# 846-XXXXX_SCH_NEO-M9N_MODULE_2_RECEIVER.net
KiCad netlist of a schematic drawn in Altium Designer
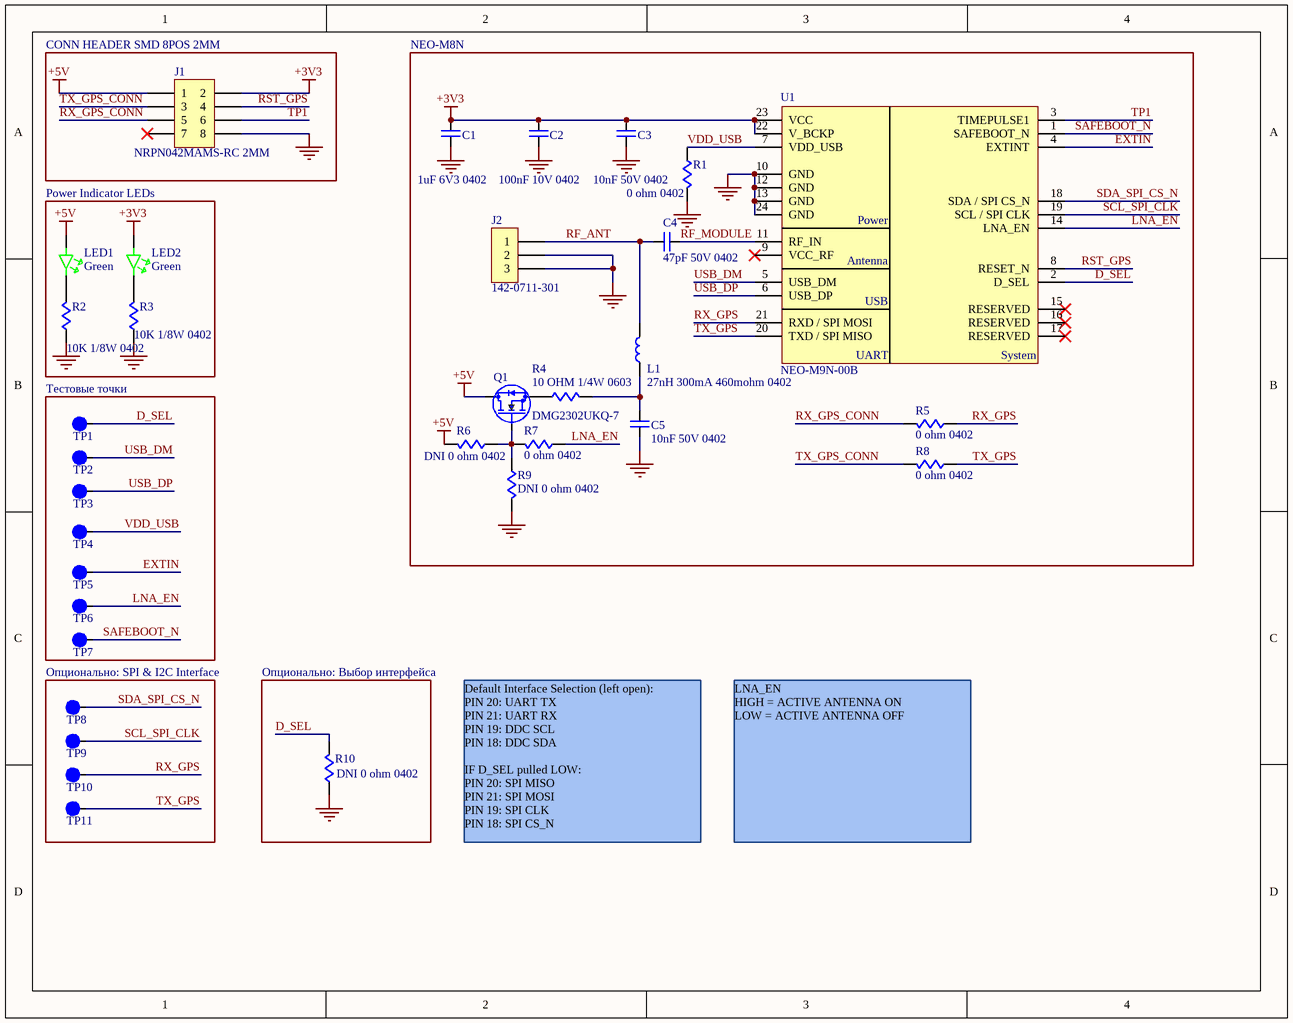
[diagram p0: 846-XXXXX_SCH_NEO-M9N_MODULE_2_RECEIVER.SchDoc]

(export (version "E")
  (design (tool "Eeschema 10.0.6"))
  (components
    (comp (ref "C1")
      (value "1uF 6V3 0402")
      (footprint "c0402")
      (description "0402 1 uF 6.3 V ±10% Tolerance X7R Multilayer Ceramic Capacitor")
      (fields
        (field (name "MANUFACTURER") "Murata")
        (field (name "MANUFACTURER PART NUMBER") "GRM155R70J105KA12J")
      )
      (libsource (lib "MyLibrary") (part "CAP CER 1UF 6.3V X7R 0402"))
    )
    (comp (ref "C2")
      (value "100nF 10V 0402")
      (footprint "c0402")
      (description "CL05 Series 0.1 uF 10 V ±10 % Tolerance X7R SMT Multilayer Ceramic Capacitor")
      (fields
        (field (name "MANUFACTURER") "Samsung")
        (field (name "MANUFACTURER PART NUMBER") "CL05B104KP5NNNC")
      )
      (libsource (lib "MyLibrary") (part "CAP CER 0.1UF 10V X7R 0402"))
    )
    (comp (ref "C3")
      (value "10nF 50V 0402")
      (footprint "c0402")
      (description "CAP CER 10000PF 50V X7R 0402")
      (fields
        (field (name "MANUFACTURER") "Murata")
        (field (name "MANUFACTURER PART NUMBER") "GCM155R71H103KA55D")
      )
      (libsource (lib "MyLibrary") (part "CAP CER 10000PF 50V X7R 0402"))
    )
    (comp (ref "C4")
      (value "47pF 50V 0402")
      (footprint "c0402")
      (description "0402 47 pF 50 V ±5 % Tolerance NP0 SMT Multilayer Ceramic Capacitor")
      (fields
        (field (name "MANUFACTURER") "Yageo")
        (field (name "MANUFACTURER PART NUMBER") "CC0402JRNPO9BN470")
      )
      (libsource (lib "MyLibrary") (part "CAP CER 47PF 50V C0G/NPO 0402"))
    )
    (comp (ref "C5")
      (value "10nF 50V 0402")
      (footprint "c0402")
      (description "CAP CER 10000PF 50V X7R 0402")
      (fields
        (field (name "MANUFACTURER") "Murata")
        (field (name "MANUFACTURER PART NUMBER") "GCM155R71H103KA55D")
      )
      (libsource (lib "MyLibrary") (part "CAP CER 10000PF 50V X7R 0402"))
    )
    (comp (ref "J1")
      (value "NRPN042MAMS-RC 2MM")
      (footprint "CONN_NRPN042MAMS-RC")
      (description "Dual Row 8 Position 2 mm Pitch Surface Mount Header")
      (fields
        (field (name "MANUFACTURER") "Sullins")
        (field (name "MANUFACTURER PART NUMBER") "NRPN042MAMS-RC")
      )
      (libsource (lib "MyLibrary") (part "CONN_NRPN042MAMS-RC"))
    )
    (comp (ref "J2")
      (value "142-0711-301")
      (footprint "CONN_131-3711-301")
      (description "Rf Coaxial Board Mount Connector")
      (fields
        (field (name "MANUFACTURER") "Bel Cinch")
        (field (name "MANUFACTURER PART NUMBER") "131-3711-301")
      )
      (libsource (lib "MyLibrary") (part "CONN_131-3711-301"))
    )
    (comp (ref "L1")
      (value "27nH 300mA 460mohm 0402")
      (footprint "L0402")
      (description "Inductor RF Chip Multi-Layer 27nH 5% 100MHz 8Q-Factor Air 300mA 460mOhm DCR 0402 Paper T/R")
      (fields
        (field (name "MANUFACTURER") "Murata")
        (field (name "MANUFACTURER PART NUMBER") "LQG15HS27NJ02D")
      )
      (libsource (lib "MyLibrary") (part "FIXED IND 27NH 350MA 460MOHM SMD"))
    )
    (comp (ref "LED1")
      (value "Green")
      (footprint "led0603")
      (description "LED High-Power Uni-Color Green 574nm 2-Pin Chip LED T/R")
      (fields
        (field (name "MANUFACTURER") "Vishay Lite-On")
        (field (name "MANUFACTURER PART NUMBER") "LTST-C190KGKT")
      )
      (libsource (lib "MyLibrary") (part "LED GREEN CLEAR CHIP SMD"))
    )
    (comp (ref "LED2")
      (value "Green")
      (footprint "led0603")
      (description "LED High-Power Uni-Color Green 574nm 2-Pin Chip LED T/R")
      (fields
        (field (name "MANUFACTURER") "Vishay Lite-On")
        (field (name "MANUFACTURER PART NUMBER") "LTST-C190KGKT")
      )
      (libsource (lib "MyLibrary") (part "LED GREEN CLEAR CHIP SMD"))
    )
    (comp (ref "Q1")
      (value "DMG2302UKQ-7")
      (footprint "SOT23")
      (description "N-Channel 20 V 2.8A (Ta) 660mW (Ta) Surface Mount SOT-23-3")
      (fields
        (field (name "MANUFACTURER") "Diodes")
        (field (name "COPYRIGHT") "Copyright (C) 2022 Ultra Librarian. All rights reserved.")
      )
      (libsource (lib "MyLibrary") (part "DMG2302UKQ-7"))
    )
    (comp (ref "R1")
      (value "0 ohm 0402")
      (footprint "r0402")
      (description "RES SMD 0 OHM JUMPER 1/16W 0402")
      (fields
        (field (name "MANUFACTURER") "Yageo")
        (field (name "MANUFACTURER PART NUMBER") "RC0402JR-070RL")
      )
      (libsource (lib "MyLibrary") (part "RES 0 OHM JUMPER 1/16W 0402"))
    )
    (comp (ref "R2")
      (value "10K 1/8W 0402")
      (footprint "r0402")
      (description "Res Thick Film 0402 10K Ohm 1% 0.125W(1/8W) ±100ppm/°C Pad SMD T/R")
      (fields
        (field (name "MANUFACTURER") "TE Connectivity")
        (field (name "MANUFACTURER PART NUMBER") "CRGP0402F10K")
      )
      (libsource (lib "MyLibrary") (part "RES 10K OHM 1% 1/8W 0402"))
    )
    (comp (ref "R3")
      (value "10K 1/8W 0402")
      (footprint "r0402")
      (description "Res Thick Film 0402 10K Ohm 1% 0.125W(1/8W) ±100ppm/°C Pad SMD T/R")
      (fields
        (field (name "MANUFACTURER") "TE Connectivity")
        (field (name "MANUFACTURER PART NUMBER") "CRGP0402F10K")
      )
      (libsource (lib "MyLibrary") (part "RES 10K OHM 1% 1/8W 0402"))
    )
    (comp (ref "R4")
      (value "10 OHM 1/4W 0603")
      (footprint "r0603")
      (description "Res Surge Chip Thick Film 0603 10 Ohm 1% 1/4W ±200ppm/°C Molded Paper T/R")
      (fields
        (field (name "MANUFACTURER") "Yageo")
        (field (name "MANUFACTURER PART NUMBER") "SR0603FR-7T10RL")
      )
      (libsource (lib "MyLibrary") (part "RES SMD 10 OHM 1% 1/4W 0603"))
    )
    (comp (ref "R5")
      (value "0 ohm 0402")
      (footprint "r0402")
      (description "RES SMD 0 OHM JUMPER 1/16W 0402")
      (fields
        (field (name "MANUFACTURER") "Yageo")
        (field (name "MANUFACTURER PART NUMBER") "RC0402JR-070RL")
      )
      (libsource (lib "MyLibrary") (part "RES 0 OHM JUMPER 1/16W 0402"))
    )
    (comp (ref "R6")
      (value "DNI 0 ohm 0402")
      (footprint "r0402")
      (description "RES SMD 0 OHM JUMPER 1/16W 0402")
      (fields
        (field (name "MANUFACTURER") "Yageo")
        (field (name "MANUFACTURER PART NUMBER") "RC0402JR-070RL")
      )
      (libsource (lib "MyLibrary") (part "RES 0 OHM JUMPER 1/16W 0402"))
    )
    (comp (ref "R7")
      (value "0 ohm 0402")
      (footprint "r0402")
      (description "RES SMD 0 OHM JUMPER 1/16W 0402")
      (fields
        (field (name "MANUFACTURER") "Yageo")
        (field (name "MANUFACTURER PART NUMBER") "RC0402JR-070RL")
      )
      (libsource (lib "MyLibrary") (part "RES 0 OHM JUMPER 1/16W 0402"))
    )
    (comp (ref "R8")
      (value "0 ohm 0402")
      (footprint "r0402")
      (description "RES SMD 0 OHM JUMPER 1/16W 0402")
      (fields
        (field (name "MANUFACTURER") "Yageo")
        (field (name "MANUFACTURER PART NUMBER") "RC0402JR-070RL")
      )
      (libsource (lib "MyLibrary") (part "RES 0 OHM JUMPER 1/16W 0402"))
    )
    (comp (ref "R9")
      (value "DNI 0 ohm 0402")
      (footprint "r0402")
      (description "RES SMD 0 OHM JUMPER 1/16W 0402")
      (fields
        (field (name "MANUFACTURER") "Yageo")
        (field (name "MANUFACTURER PART NUMBER") "RC0402JR-070RL")
      )
      (libsource (lib "MyLibrary") (part "RES 0 OHM JUMPER 1/16W 0402"))
    )
    (comp (ref "R10")
      (value "DNI 0 ohm 0402")
      (footprint "r0402")
      (description "RES SMD 0 OHM JUMPER 1/16W 0402")
      (fields
        (field (name "MANUFACTURER") "Yageo")
        (field (name "MANUFACTURER PART NUMBER") "RC0402JR-070RL")
      )
      (libsource (lib "MyLibrary") (part "RES 0 OHM JUMPER 1/16W 0402"))
    )
    (comp (ref "TP1")
      (value "1MM")
      (footprint "TP1MM")
      (description "Test Point 1MM diameter")
      (libsource (lib "MyLibrary") (part "TP_1MM"))
    )
    (comp (ref "TP2")
      (value "1MM")
      (footprint "TP1MM")
      (description "Test Point 1MM diameter")
      (libsource (lib "MyLibrary") (part "TP_1MM"))
    )
    (comp (ref "TP3")
      (value "1MM")
      (footprint "TP1MM")
      (description "Test Point 1MM diameter")
      (libsource (lib "MyLibrary") (part "TP_1MM"))
    )
    (comp (ref "TP4")
      (value "1MM")
      (footprint "TP1MM")
      (description "Test Point 1MM diameter")
      (libsource (lib "MyLibrary") (part "TP_1MM"))
    )
    (comp (ref "TP5")
      (value "1MM")
      (footprint "TP1MM")
      (description "Test Point 1MM diameter")
      (libsource (lib "MyLibrary") (part "TP_1MM"))
    )
    (comp (ref "TP6")
      (value "1MM")
      (footprint "TP1MM")
      (description "Test Point 1MM diameter")
      (libsource (lib "MyLibrary") (part "TP_1MM"))
    )
    (comp (ref "TP7")
      (value "1MM")
      (footprint "TP1MM")
      (description "Test Point 1MM diameter")
      (libsource (lib "MyLibrary") (part "TP_1MM"))
    )
    (comp (ref "TP8")
      (value "1MM")
      (footprint "TP1MM")
      (description "Test Point 1MM diameter")
      (libsource (lib "MyLibrary") (part "TP_1MM"))
    )
    (comp (ref "TP9")
      (value "1MM")
      (footprint "TP1MM")
      (description "Test Point 1MM diameter")
      (libsource (lib "MyLibrary") (part "TP_1MM"))
    )
    (comp (ref "TP10")
      (value "1MM")
      (footprint "TP1MM")
      (description "Test Point 1MM diameter")
      (libsource (lib "MyLibrary") (part "TP_1MM"))
    )
    (comp (ref "TP11")
      (value "1MM")
      (footprint "TP1MM")
      (description "Test Point 1MM diameter")
      (libsource (lib "MyLibrary") (part "TP_1MM"))
    )
    (comp (ref "U1")
      (value "NEO-M9N-00B")
      (footprint "IC_NEO-M9N")
      (description "GNSS module, Flash, TCXO, SAW, LNA, LCC, 12x16 mm Professional Grade")
      (fields (field (name "MANUFACTURER") "u-blox"))
      (libsource (lib "MyLibrary") (part "IC NEO-M9N-00B"))
    )
  )
  (nets
    (net (code "1") (name "+3V3") (class "Default")
      (node (ref "C1") (pin "2") (pinfunction "2_2") (pintype "passive"))
      (node (ref "C2") (pin "2") (pinfunction "2_2") (pintype "passive"))
      (node (ref "C3") (pin "2") (pinfunction "2_2") (pintype "passive"))
      (node (ref "J1") (pin "2") (pinfunction "2_2") (pintype "passive"))
      (node (ref "LED2") (pin "1") (pinfunction "1_1") (pintype "passive"))
      (node (ref "U1") (pin "22") (pinfunction "V_BCKP_22") (pintype "passive"))
      (node (ref "U1") (pin "23") (pinfunction "VCC_23") (pintype "passive"))
    )
    (net (code "2") (name "+5V") (class "Default")
      (node (ref "J1") (pin "1") (pinfunction "1_1") (pintype "passive"))
      (node (ref "LED1") (pin "1") (pinfunction "1_1") (pintype "passive"))
      (node (ref "Q1") (pin "2") (pinfunction "D_2") (pintype "passive"))
      (node (ref "R6") (pin "2") (pinfunction "2_2") (pintype "passive"))
    )
    (net (code "3") (name "/D_SEL") (class "Default")
      (node (ref "R10") (pin "2") (pinfunction "2_2") (pintype "passive"))
      (node (ref "TP1") (pin "1") (pinfunction "1_1") (pintype "passive"))
      (node (ref "U1") (pin "2") (pinfunction "D_SEL_2") (pintype "passive"))
    )
    (net (code "4") (name "/EXTIN") (class "Default")
      (node (ref "TP5") (pin "1") (pinfunction "1_1") (pintype "passive"))
      (node (ref "U1") (pin "4") (pinfunction "EXTINT_4") (pintype "passive"))
    )
    (net (code "5") (name "/LNA_EN") (class "Default")
      (node (ref "R7") (pin "1") (pinfunction "1_1") (pintype "passive"))
      (node (ref "TP6") (pin "1") (pinfunction "1_1") (pintype "passive"))
      (node (ref "U1") (pin "14") (pinfunction "LNA_EN_14") (pintype "passive"))
    )
    (net (code "6") (name "/RF_ANT") (class "Default")
      (node (ref "C4") (pin "1") (pinfunction "1_1") (pintype "passive"))
      (node (ref "J2") (pin "1") (pinfunction "1_1") (pintype "passive"))
      (node (ref "L1") (pin "2") (pinfunction "2_2") (pintype "passive"))
    )
    (net (code "7") (name "/RF_MODULE") (class "Default")
      (node (ref "C4") (pin "2") (pinfunction "2_2") (pintype "passive"))
      (node (ref "U1") (pin "11") (pinfunction "RF_IN_11") (pintype "passive"))
    )
    (net (code "8") (name "/RST_GPS") (class "Default")
      (node (ref "J1") (pin "4") (pinfunction "4_4") (pintype "passive"))
      (node (ref "U1") (pin "8") (pinfunction "RESET_N_8") (pintype "passive"))
    )
    (net (code "9") (name "/RX_GPS") (class "Default")
      (node (ref "R5") (pin "1") (pinfunction "1_1") (pintype "passive"))
      (node (ref "TP10") (pin "1") (pinfunction "1_1") (pintype "passive"))
      (node (ref "U1") (pin "21") (pinfunction "RXD_/_SPI_MOSI_21") (pintype "passive"))
    )
    (net (code "10") (name "/RX_GPS_CONN") (class "Default")
      (node (ref "J1") (pin "5") (pinfunction "5_5") (pintype "passive"))
      (node (ref "R5") (pin "2") (pinfunction "2_2") (pintype "passive"))
    )
    (net (code "11") (name "/SAFEBOOT_N") (class "Default")
      (node (ref "TP7") (pin "1") (pinfunction "1_1") (pintype "passive"))
      (node (ref "U1") (pin "1") (pinfunction "SAFEBOOT_N_1") (pintype "passive"))
    )
    (net (code "12") (name "/SCL_SPI_CLK") (class "Default")
      (node (ref "TP9") (pin "1") (pinfunction "1_1") (pintype "passive"))
      (node (ref "U1") (pin "19") (pinfunction "SCL_/_SPI_CLK_19") (pintype "passive"))
    )
    (net (code "13") (name "/SDA_SPI_CS_N") (class "Default")
      (node (ref "TP8") (pin "1") (pinfunction "1_1") (pintype "passive"))
      (node (ref "U1") (pin "18") (pinfunction "SDA_/_SPI_CS_N_18") (pintype "passive"))
    )
    (net (code "14") (name "/TP1") (class "Default")
      (node (ref "J1") (pin "6") (pinfunction "6_6") (pintype "passive"))
      (node (ref "U1") (pin "3") (pinfunction "TIMEPULSE1_3") (pintype "passive"))
    )
    (net (code "15") (name "/TX_GPS") (class "Default")
      (node (ref "R8") (pin "1") (pinfunction "1_1") (pintype "passive"))
      (node (ref "TP11") (pin "1") (pinfunction "1_1") (pintype "passive"))
      (node (ref "U1") (pin "20") (pinfunction "TXD_/_SPI_MISO_20") (pintype "passive"))
    )
    (net (code "16") (name "/TX_GPS_CONN") (class "Default")
      (node (ref "J1") (pin "3") (pinfunction "3_3") (pintype "passive"))
      (node (ref "R8") (pin "2") (pinfunction "2_2") (pintype "passive"))
    )
    (net (code "17") (name "/USB_DM") (class "Default")
      (node (ref "TP2") (pin "1") (pinfunction "1_1") (pintype "passive"))
      (node (ref "U1") (pin "5") (pinfunction "USB_DM_5") (pintype "passive"))
    )
    (net (code "18") (name "/USB_DP") (class "Default")
      (node (ref "TP3") (pin "1") (pinfunction "1_1") (pintype "passive"))
      (node (ref "U1") (pin "6") (pinfunction "USB_DP_6") (pintype "passive"))
    )
    (net (code "19") (name "/VDD_USB") (class "Default")
      (node (ref "R1") (pin "1") (pinfunction "1_1") (pintype "passive"))
      (node (ref "TP4") (pin "1") (pinfunction "1_1") (pintype "passive"))
      (node (ref "U1") (pin "7") (pinfunction "VDD_USB_7") (pintype "passive"))
    )
    (net (code "20") (name "GND") (class "Default")
      (node (ref "C1") (pin "1") (pinfunction "1_1") (pintype "passive"))
      (node (ref "C2") (pin "1") (pinfunction "1_1") (pintype "passive"))
      (node (ref "C3") (pin "1") (pinfunction "1_1") (pintype "passive"))
      (node (ref "C5") (pin "1") (pinfunction "1_1") (pintype "passive"))
      (node (ref "J1") (pin "8") (pinfunction "8_8") (pintype "passive"))
      (node (ref "J2") (pin "2") (pinfunction "2_2") (pintype "passive"))
      (node (ref "J2") (pin "3") (pinfunction "3_3") (pintype "passive"))
      (node (ref "R1") (pin "2") (pinfunction "2_2") (pintype "passive"))
      (node (ref "R10") (pin "1") (pinfunction "1_1") (pintype "passive"))
      (node (ref "R2") (pin "1") (pinfunction "1_1") (pintype "passive"))
      (node (ref "R3") (pin "1") (pinfunction "1_1") (pintype "passive"))
      (node (ref "R9") (pin "2") (pinfunction "2_2") (pintype "passive"))
      (node (ref "U1") (pin "10") (pinfunction "GND_10") (pintype "passive"))
      (node (ref "U1") (pin "12") (pinfunction "GND_12") (pintype "passive"))
      (node (ref "U1") (pin "13") (pinfunction "GND_13") (pintype "passive"))
      (node (ref "U1") (pin "24") (pinfunction "GND_24") (pintype "passive"))
    )
    (net (code "21") (name "Net-(C5-Pad2)") (class "Default")
      (node (ref "C5") (pin "2") (pinfunction "2_2") (pintype "passive"))
      (node (ref "L1") (pin "1") (pinfunction "1_1") (pintype "passive"))
      (node (ref "R4") (pin "2") (pinfunction "2_2") (pintype "passive"))
    )
    (net (code "22") (name "Net-(LED1-Pad2)") (class "Default")
      (node (ref "LED1") (pin "2") (pinfunction "2_2") (pintype "passive"))
      (node (ref "R2") (pin "2") (pinfunction "2_2") (pintype "passive"))
    )
    (net (code "23") (name "Net-(LED2-Pad2)") (class "Default")
      (node (ref "LED2") (pin "2") (pinfunction "2_2") (pintype "passive"))
      (node (ref "R3") (pin "2") (pinfunction "2_2") (pintype "passive"))
    )
    (net (code "24") (name "Net-(Q1-G)") (class "Default")
      (node (ref "Q1") (pin "1") (pinfunction "G_1") (pintype "passive"))
      (node (ref "R6") (pin "1") (pinfunction "1_1") (pintype "passive"))
      (node (ref "R7") (pin "2") (pinfunction "2_2") (pintype "passive"))
      (node (ref "R9") (pin "1") (pinfunction "1_1") (pintype "passive"))
    )
    (net (code "25") (name "Net-(Q1-S)") (class "Default")
      (node (ref "Q1") (pin "3") (pinfunction "S_3") (pintype "passive"))
      (node (ref "R4") (pin "1") (pinfunction "1_1") (pintype "passive"))
    )
    (net (code "26") (name "unconnected-(J1-Pad7)") (class "Default")
      (node (ref "J1") (pin "7") (pinfunction "7_7") (pintype "passive+no_connect"))
    )
    (net (code "27") (name "unconnected-(U1-RESERVED-Pad15)") (class "Default")
      (node (ref "U1") (pin "15") (pinfunction "RESERVED_15") (pintype "passive+no_connect"))
    )
    (net (code "28") (name "unconnected-(U1-RESERVED-Pad16)") (class "Default")
      (node (ref "U1") (pin "16") (pinfunction "RESERVED_16") (pintype "passive+no_connect"))
    )
    (net (code "29") (name "unconnected-(U1-RESERVED-Pad17)") (class "Default")
      (node (ref "U1") (pin "17") (pinfunction "RESERVED_17") (pintype "passive+no_connect"))
    )
    (net (code "30") (name "unconnected-(U1-VCC_RF-Pad9)") (class "Default")
      (node (ref "U1") (pin "9") (pinfunction "VCC_RF_9") (pintype "passive+no_connect"))
    )
  )
)
